# prog.net
KiCad netlist of a schematic drawn in EAGLE
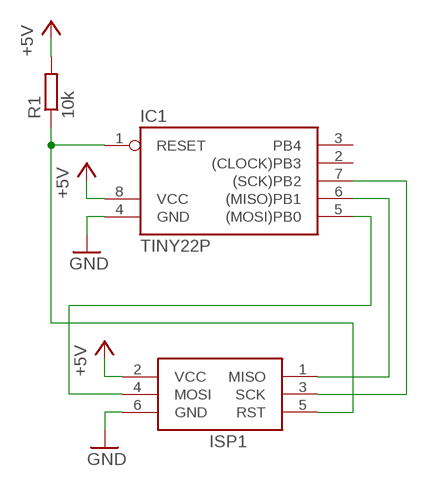
[diagram p0: schematic, sheet 1]

(export (version "E")
  (design (tool "Eeschema 10.0.6"))
  (components
    (comp (ref "IC1")
      (value "TINY22P")
      (footprint "eagle-import:DIL08")
      (libsource (lib "eagle-import") (part "TINY22P"))
    )
    (comp (ref "ISP1")
      (value "AVRISP-6")
      (footprint "eagle-import:AVRISP")
      (libsource (lib "eagle-import") (part "AVRISP-6"))
    )
    (comp (ref "R1")
      (value "10k")
      (footprint "eagle-import:0204_7")
      (libsource (lib "eagle-import") (part "R-EU_0204/7"))
    )
  )
  (nets
    (net (code "1") (name "+5V") (class "Default")
      (node (ref "IC1") (pin "8") (pinfunction "VCC_8") (pintype "power_in"))
      (node (ref "ISP1") (pin "2") (pinfunction "VCC_2") (pintype "power_in"))
      (node (ref "R1") (pin "2") (pinfunction "2_2") (pintype "passive"))
    )
    (net (code "2") (name "GND") (class "Default")
      (node (ref "IC1") (pin "4") (pinfunction "GND_4") (pintype "power_in"))
      (node (ref "ISP1") (pin "6") (pinfunction "GND_6") (pintype "power_in"))
    )
    (net (code "3") (name "Net-(IC1-(MISO)PB1)") (class "Default")
      (node (ref "IC1") (pin "6") (pinfunction "(MISO)PB1_6") (pintype "bidirectional"))
      (node (ref "ISP1") (pin "1") (pinfunction "MISO_1") (pintype "input"))
    )
    (net (code "4") (name "Net-(IC1-(MOSI)PB0)") (class "Default")
      (node (ref "IC1") (pin "5") (pinfunction "(MOSI)PB0_5") (pintype "bidirectional"))
      (node (ref "ISP1") (pin "4") (pinfunction "MOSI_4") (pintype "output"))
    )
    (net (code "5") (name "Net-(IC1-(SCK)PB2)") (class "Default")
      (node (ref "IC1") (pin "7") (pinfunction "(SCK)PB2_7") (pintype "bidirectional"))
      (node (ref "ISP1") (pin "3") (pinfunction "SCK_3") (pintype "output"))
    )
    (net (code "6") (name "Net-(IC1-RESET)") (class "Default")
      (node (ref "IC1") (pin "1") (pinfunction "RESET_1") (pintype "input"))
      (node (ref "ISP1") (pin "5") (pinfunction "RST_5") (pintype "output"))
      (node (ref "R1") (pin "1") (pinfunction "1_1") (pintype "passive"))
    )
    (net (code "7") (name "unconnected-(IC1-(CLOCK)PB3-Pad2)") (class "Default")
      (node (ref "IC1") (pin "2") (pinfunction "(CLOCK)PB3_2") (pintype "bidirectional"))
    )
    (net (code "8") (name "unconnected-(IC1-PB4-Pad3)") (class "Default")
      (node (ref "IC1") (pin "3") (pinfunction "PB4_3") (pintype "bidirectional"))
    )
  )
)
